# Sheet1.net
KiCad netlist of a schematic drawn in Altium Designer
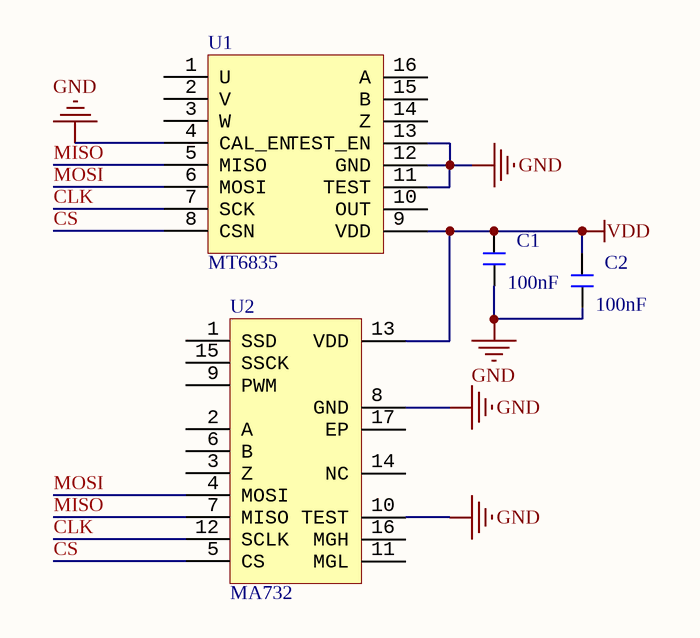
[diagram p0: Sheet1.SchDoc]

(export (version "E")
  (design (tool "Eeschema 10.0.6"))
  (components
    (comp (ref "C1")
      (value "100nF")
      (footprint "C 0402_L")
      (description "无极性贴片电容")
      (fields (field (name "版权归属") "源创客"))
      (libsource (lib "3.1   - 电阻-电容-电感") (part "C"))
    )
    (comp (ref "C2")
      (value "100nF")
      (footprint "C 0402_L")
      (description "无极性贴片电容")
      (fields (field (name "版权归属") "源创客"))
      (libsource (lib "3.1   - 电阻-电容-电感") (part "C"))
    )
    (comp (ref "U1")
      (value "MT6835")
      (footprint "TSSOP16_L")
      (description "21bit磁编码芯片")
      (libsource (lib "1.1   - IC芯片") (part "MT6835"))
    )
    (comp (ref "U2")
      (value "MA732")
      (footprint "QFN16 3X3")
      (description "14bit编码器芯片")
      (libsource (lib "1.1   - IC芯片") (part "MA732"))
    )
  )
  (nets
    (net (code "1") (name "/CLK") (class "Default")
      (node (ref "U1") (pin "7") (pinfunction "SCK_7") (pintype "passive"))
      (node (ref "U2") (pin "12") (pinfunction "SCLK_12") (pintype "passive"))
    )
    (net (code "2") (name "/CS") (class "Default")
      (node (ref "U1") (pin "8") (pinfunction "CSN_8") (pintype "passive"))
      (node (ref "U2") (pin "5") (pinfunction "CS_5") (pintype "passive"))
    )
    (net (code "3") (name "/MISO") (class "Default")
      (node (ref "U1") (pin "5") (pinfunction "MISO_5") (pintype "passive"))
      (node (ref "U2") (pin "7") (pinfunction "MISO_7") (pintype "passive"))
    )
    (net (code "4") (name "/MOSI") (class "Default")
      (node (ref "U1") (pin "6") (pinfunction "MOSI_6") (pintype "passive"))
      (node (ref "U2") (pin "4") (pinfunction "MOSI_4") (pintype "passive"))
    )
    (net (code "5") (name "GND") (class "Default")
      (node (ref "C1") (pin "1") (pinfunction "1_1") (pintype "passive"))
      (node (ref "C2") (pin "1") (pinfunction "1_1") (pintype "passive"))
      (node (ref "U1") (pin "11") (pinfunction "TEST_11") (pintype "passive"))
      (node (ref "U1") (pin "12") (pinfunction "GND_12") (pintype "passive"))
      (node (ref "U1") (pin "13") (pinfunction "TEST_EN_13") (pintype "passive"))
      (node (ref "U1") (pin "4") (pinfunction "CAL_EN_4") (pintype "passive"))
      (node (ref "U2") (pin "10") (pinfunction "TEST_10") (pintype "passive"))
      (node (ref "U2") (pin "8") (pinfunction "GND_8") (pintype "passive"))
    )
    (net (code "6") (name "VDD") (class "Default")
      (node (ref "C1") (pin "2") (pinfunction "2_2") (pintype "passive"))
      (node (ref "C2") (pin "2") (pinfunction "2_2") (pintype "passive"))
      (node (ref "U1") (pin "9") (pinfunction "VDD_9") (pintype "passive"))
      (node (ref "U2") (pin "13") (pinfunction "VDD_13") (pintype "passive"))
    )
    (net (code "7") (name "unconnected-(U1-A-Pad16)") (class "Default")
      (node (ref "U1") (pin "16") (pinfunction "A_16") (pintype "passive"))
    )
    (net (code "8") (name "unconnected-(U1-B-Pad15)") (class "Default")
      (node (ref "U1") (pin "15") (pinfunction "B_15") (pintype "passive"))
    )
    (net (code "9") (name "unconnected-(U1-OUT-Pad10)") (class "Default")
      (node (ref "U1") (pin "10") (pinfunction "OUT_10") (pintype "passive"))
    )
    (net (code "10") (name "unconnected-(U1-U-Pad1)") (class "Default")
      (node (ref "U1") (pin "1") (pinfunction "U_1") (pintype "passive"))
    )
    (net (code "11") (name "unconnected-(U1-V-Pad2)") (class "Default")
      (node (ref "U1") (pin "2") (pinfunction "V_2") (pintype "passive"))
    )
    (net (code "12") (name "unconnected-(U1-W-Pad3)") (class "Default")
      (node (ref "U1") (pin "3") (pinfunction "W_3") (pintype "passive"))
    )
    (net (code "13") (name "unconnected-(U1-Z-Pad14)") (class "Default")
      (node (ref "U1") (pin "14") (pinfunction "Z_14") (pintype "passive"))
    )
    (net (code "14") (name "unconnected-(U2-A-Pad2)") (class "Default")
      (node (ref "U2") (pin "2") (pinfunction "A_2") (pintype "passive"))
    )
    (net (code "15") (name "unconnected-(U2-B-Pad6)") (class "Default")
      (node (ref "U2") (pin "6") (pinfunction "B_6") (pintype "passive"))
    )
    (net (code "16") (name "unconnected-(U2-EP-Pad17)") (class "Default")
      (node (ref "U2") (pin "17") (pinfunction "EP_17") (pintype "passive"))
    )
    (net (code "17") (name "unconnected-(U2-MGH-Pad16)") (class "Default")
      (node (ref "U2") (pin "16") (pinfunction "MGH_16") (pintype "passive"))
    )
    (net (code "18") (name "unconnected-(U2-MGL-Pad11)") (class "Default")
      (node (ref "U2") (pin "11") (pinfunction "MGL_11") (pintype "passive"))
    )
    (net (code "19") (name "unconnected-(U2-NC-Pad14)") (class "Default")
      (node (ref "U2") (pin "14") (pinfunction "NC_14") (pintype "passive"))
    )
    (net (code "20") (name "unconnected-(U2-PWM-Pad9)") (class "Default")
      (node (ref "U2") (pin "9") (pinfunction "PWM_9") (pintype "passive"))
    )
    (net (code "21") (name "unconnected-(U2-SSCK-Pad15)") (class "Default")
      (node (ref "U2") (pin "15") (pinfunction "SSCK_15") (pintype "passive"))
    )
    (net (code "22") (name "unconnected-(U2-SSD-Pad1)") (class "Default")
      (node (ref "U2") (pin "1") (pinfunction "SSD_1") (pintype "passive"))
    )
    (net (code "23") (name "unconnected-(U2-Z-Pad3)") (class "Default")
      (node (ref "U2") (pin "3") (pinfunction "Z_3") (pintype "passive"))
    )
  )
)
